# nguyen_ly.net
KiCad netlist of a schematic drawn in Altium Designer
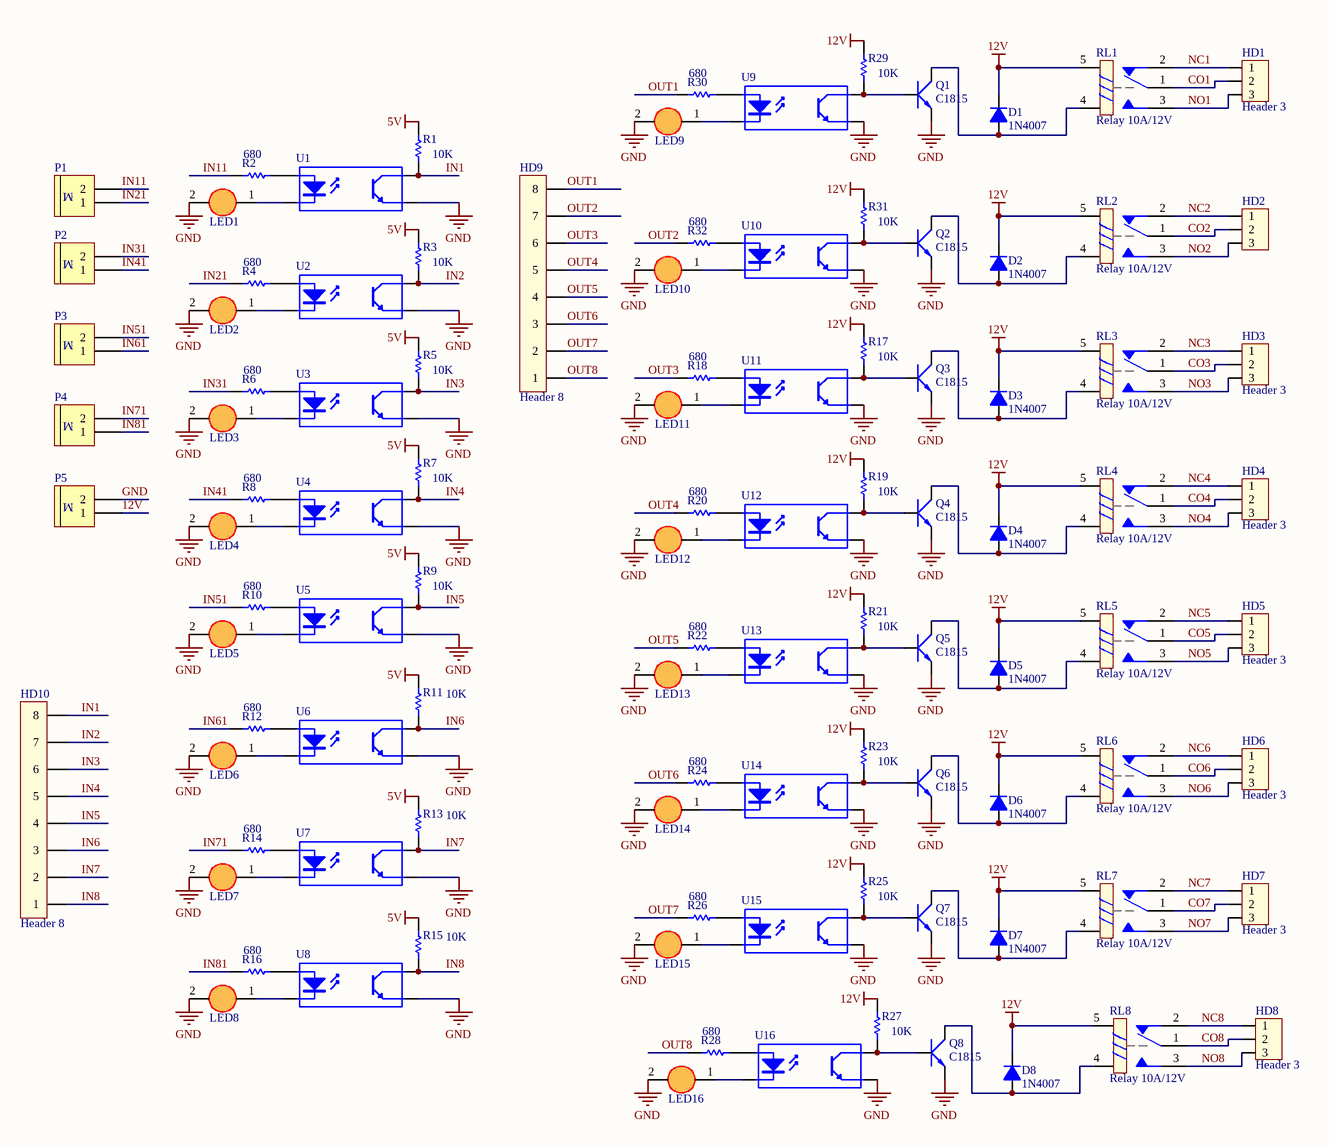
[diagram p0: nguyen ly.SchDoc]

(export (version "E")
  (design (tool "Eeschema 10.0.6"))
  (components
    (comp (ref "D1")
      (value "1N4007")
      (footprint "D1A")
      (description "Diode 1A")
      (libsource (lib "syhaunguyen") (part "D1A"))
    )
    (comp (ref "D2")
      (value "1N4007")
      (footprint "D1A")
      (description "Diode 1A")
      (libsource (lib "syhaunguyen") (part "D1A"))
    )
    (comp (ref "D3")
      (value "1N4007")
      (footprint "D1A")
      (description "Diode 1A")
      (libsource (lib "syhaunguyen") (part "D1A"))
    )
    (comp (ref "D4")
      (value "1N4007")
      (footprint "D1A")
      (description "Diode 1A")
      (libsource (lib "syhaunguyen") (part "D1A"))
    )
    (comp (ref "D5")
      (value "1N4007")
      (footprint "D1A")
      (description "Diode 1A")
      (libsource (lib "syhaunguyen") (part "D1A"))
    )
    (comp (ref "D6")
      (value "1N4007")
      (footprint "D1A")
      (description "Diode 1A")
      (libsource (lib "syhaunguyen") (part "D1A"))
    )
    (comp (ref "D7")
      (value "1N4007")
      (footprint "D1A")
      (description "Diode 1A")
      (libsource (lib "syhaunguyen") (part "D1A"))
    )
    (comp (ref "D8")
      (value "1N4007")
      (footprint "D1A")
      (description "Diode 1A")
      (libsource (lib "syhaunguyen") (part "D1A"))
    )
    (comp (ref "HD1")
      (value "Header 3")
      (footprint "HED3")
      (description "Header 3 (Green)")
      (libsource (lib "syhaunguyen") (part "Hed3"))
    )
    (comp (ref "HD2")
      (value "Header 3")
      (footprint "HED3")
      (description "Header 3 (Green)")
      (libsource (lib "syhaunguyen") (part "Hed3"))
    )
    (comp (ref "HD3")
      (value "Header 3")
      (footprint "HED3")
      (description "Header 3 (Green)")
      (libsource (lib "syhaunguyen") (part "Hed3"))
    )
    (comp (ref "HD4")
      (value "Header 3")
      (footprint "HED3")
      (description "Header 3 (Green)")
      (libsource (lib "syhaunguyen") (part "Hed3"))
    )
    (comp (ref "HD5")
      (value "Header 3")
      (footprint "HED3")
      (description "Header 3 (Green)")
      (libsource (lib "syhaunguyen") (part "Hed3"))
    )
    (comp (ref "HD6")
      (value "Header 3")
      (footprint "HED3")
      (description "Header 3 (Green)")
      (libsource (lib "syhaunguyen") (part "Hed3"))
    )
    (comp (ref "HD7")
      (value "Header 3")
      (footprint "HED3")
      (description "Header 3 (Green)")
      (libsource (lib "syhaunguyen") (part "Hed3"))
    )
    (comp (ref "HD8")
      (value "Header 3")
      (footprint "HED3")
      (description "Header 3 (Green)")
      (libsource (lib "syhaunguyen") (part "Hed3"))
    )
    (comp (ref "HD9")
      (value "Header 8")
      (footprint "HED8V")
      (description "Header 8 Vit Broad")
      (libsource (lib "syhaunguyen") (part "HED8V"))
    )
    (comp (ref "HD10")
      (value "Header 8")
      (footprint "HED8V")
      (description "Header 8 Vit Broad")
      (libsource (lib "syhaunguyen") (part "HED8V"))
    )
    (comp (ref "LED1")
      (value "LED3")
      (footprint "LED3mm")
      (description "LED 3mm")
      (libsource (lib "Cty1") (part "LED 3mm"))
    )
    (comp (ref "LED2")
      (value "LED3")
      (footprint "LED3mm")
      (description "LED 3mm")
      (libsource (lib "Cty1") (part "LED 3mm"))
    )
    (comp (ref "LED3")
      (value "LED3")
      (footprint "LED3mm")
      (description "LED 3mm")
      (libsource (lib "Cty1") (part "LED 3mm"))
    )
    (comp (ref "LED4")
      (value "LED3")
      (footprint "LED3mm")
      (description "LED 3mm")
      (libsource (lib "Cty1") (part "LED 3mm"))
    )
    (comp (ref "LED5")
      (value "LED3")
      (footprint "LED3mm")
      (description "LED 3mm")
      (libsource (lib "Cty1") (part "LED 3mm"))
    )
    (comp (ref "LED6")
      (value "LED3")
      (footprint "LED3mm")
      (description "LED 3mm")
      (libsource (lib "Cty1") (part "LED 3mm"))
    )
    (comp (ref "LED7")
      (value "LED3")
      (footprint "LED3mm")
      (description "LED 3mm")
      (libsource (lib "Cty1") (part "LED 3mm"))
    )
    (comp (ref "LED8")
      (value "LED3")
      (footprint "LED3mm")
      (description "LED 3mm")
      (libsource (lib "Cty1") (part "LED 3mm"))
    )
    (comp (ref "LED9")
      (value "LED3")
      (footprint "LED3mm")
      (description "LED 3mm")
      (libsource (lib "Cty1") (part "LED 3mm"))
    )
    (comp (ref "LED10")
      (value "LED3")
      (footprint "LED3mm")
      (description "LED 3mm")
      (libsource (lib "Cty1") (part "LED 3mm"))
    )
    (comp (ref "LED11")
      (value "LED3")
      (footprint "LED3mm")
      (description "LED 3mm")
      (libsource (lib "Cty1") (part "LED 3mm"))
    )
    (comp (ref "LED12")
      (value "LED3")
      (footprint "LED3mm")
      (description "LED 3mm")
      (libsource (lib "Cty1") (part "LED 3mm"))
    )
    (comp (ref "LED13")
      (value "LED3")
      (footprint "LED3mm")
      (description "LED 3mm")
      (libsource (lib "Cty1") (part "LED 3mm"))
    )
    (comp (ref "LED14")
      (value "LED3")
      (footprint "LED3mm")
      (description "LED 3mm")
      (libsource (lib "Cty1") (part "LED 3mm"))
    )
    (comp (ref "LED15")
      (value "LED3")
      (footprint "LED3mm")
      (description "LED 3mm")
      (libsource (lib "Cty1") (part "LED 3mm"))
    )
    (comp (ref "LED16")
      (value "LED3")
      (footprint "LED3mm")
      (description "LED 3mm")
      (libsource (lib "Cty1") (part "LED 3mm"))
    )
    (comp (ref "P1")
      (value "Header 2 - M")
      (footprint "Medium - Header 2")
      (description "Header, 2-Pin, Medium")
      (fields (field (name "PUBLISHER") "Altium Limited"))
      (libsource (lib "Cty1") (part "Header 2 - M"))
    )
    (comp (ref "P2")
      (value "Header 2 - M")
      (footprint "Medium - Header 2")
      (description "Header, 2-Pin, Medium")
      (fields (field (name "PUBLISHER") "Altium Limited"))
      (libsource (lib "Cty1") (part "Header 2 - M"))
    )
    (comp (ref "P3")
      (value "Header 2 - M")
      (footprint "Medium - Header 2")
      (description "Header, 2-Pin, Medium")
      (fields (field (name "PUBLISHER") "Altium Limited"))
      (libsource (lib "Cty1") (part "Header 2 - M"))
    )
    (comp (ref "P4")
      (value "Header 2 - M")
      (footprint "Medium - Header 2")
      (description "Header, 2-Pin, Medium")
      (fields (field (name "PUBLISHER") "Altium Limited"))
      (libsource (lib "Cty1") (part "Header 2 - M"))
    )
    (comp (ref "P5")
      (value "Header 2 - M")
      (footprint "Medium - Header 2")
      (description "Header, 2-Pin, Medium")
      (fields (field (name "PUBLISHER") "Altium Limited"))
      (libsource (lib "Cty1") (part "Header 2 - M"))
    )
    (comp (ref "Q1")
      (value "C1815")
      (footprint "QTO-92")
      (description "NPN 600mW, ECB")
      (libsource (lib "syhaunguyen") (part "C1815"))
    )
    (comp (ref "Q2")
      (value "C1815")
      (footprint "QTO-92")
      (description "NPN 600mW, ECB")
      (libsource (lib "syhaunguyen") (part "C1815"))
    )
    (comp (ref "Q3")
      (value "C1815")
      (footprint "QTO-92")
      (description "NPN 600mW, ECB")
      (libsource (lib "syhaunguyen") (part "C1815"))
    )
    (comp (ref "Q4")
      (value "C1815")
      (footprint "QTO-92")
      (description "NPN 600mW, ECB")
      (libsource (lib "syhaunguyen") (part "C1815"))
    )
    (comp (ref "Q5")
      (value "C1815")
      (footprint "QTO-92")
      (description "NPN 600mW, ECB")
      (libsource (lib "syhaunguyen") (part "C1815"))
    )
    (comp (ref "Q6")
      (value "C1815")
      (footprint "QTO-92")
      (description "NPN 600mW, ECB")
      (libsource (lib "syhaunguyen") (part "C1815"))
    )
    (comp (ref "Q7")
      (value "C1815")
      (footprint "QTO-92")
      (description "NPN 600mW, ECB")
      (libsource (lib "syhaunguyen") (part "C1815"))
    )
    (comp (ref "Q8")
      (value "C1815")
      (footprint "QTO-92")
      (description "NPN 600mW, ECB")
      (libsource (lib "syhaunguyen") (part "C1815"))
    )
    (comp (ref "R1")
      (value "10K")
      (footprint "AXIAL-0.3")
      (description "Resistor")
      (fields (field (name "Comment") "Res1") (field (name "PUBLISHER") "Altium Limited"))
      (libsource (lib "Miscellaneous Devices") (part "Res1"))
    )
    (comp (ref "R2")
      (value "680")
      (footprint "AXIAL-0.3")
      (description "Resistor")
      (fields (field (name "Comment") "Res1") (field (name "PUBLISHER") "Altium Limited"))
      (libsource (lib "Miscellaneous Devices") (part "Res1"))
    )
    (comp (ref "R3")
      (value "10K")
      (footprint "AXIAL-0.3")
      (description "Resistor")
      (fields (field (name "Comment") "Res1") (field (name "PUBLISHER") "Altium Limited"))
      (libsource (lib "Miscellaneous Devices") (part "Res1"))
    )
    (comp (ref "R4")
      (value "680")
      (footprint "AXIAL-0.3")
      (description "Resistor")
      (fields (field (name "Comment") "Res1") (field (name "PUBLISHER") "Altium Limited"))
      (libsource (lib "Miscellaneous Devices") (part "Res1"))
    )
    (comp (ref "R5")
      (value "10K")
      (footprint "AXIAL-0.3")
      (description "Resistor")
      (fields (field (name "Comment") "Res1") (field (name "PUBLISHER") "Altium Limited"))
      (libsource (lib "Miscellaneous Devices") (part "Res1"))
    )
    (comp (ref "R6")
      (value "680")
      (footprint "AXIAL-0.3")
      (description "Resistor")
      (fields (field (name "Comment") "Res1") (field (name "PUBLISHER") "Altium Limited"))
      (libsource (lib "Miscellaneous Devices") (part "Res1"))
    )
    (comp (ref "R7")
      (value "10K")
      (footprint "AXIAL-0.3")
      (description "Resistor")
      (fields (field (name "Comment") "Res1") (field (name "PUBLISHER") "Altium Limited"))
      (libsource (lib "Miscellaneous Devices") (part "Res1"))
    )
    (comp (ref "R8")
      (value "680")
      (footprint "AXIAL-0.3")
      (description "Resistor")
      (fields (field (name "Comment") "Res1") (field (name "PUBLISHER") "Altium Limited"))
      (libsource (lib "Miscellaneous Devices") (part "Res1"))
    )
    (comp (ref "R9")
      (value "10K")
      (footprint "AXIAL-0.3")
      (description "Resistor")
      (fields (field (name "Comment") "Res1") (field (name "PUBLISHER") "Altium Limited"))
      (libsource (lib "Miscellaneous Devices") (part "Res1"))
    )
    (comp (ref "R10")
      (value "680")
      (footprint "AXIAL-0.3")
      (description "Resistor")
      (fields (field (name "Comment") "Res1") (field (name "PUBLISHER") "Altium Limited"))
      (libsource (lib "Miscellaneous Devices") (part "Res1"))
    )
    (comp (ref "R11")
      (value "10K")
      (footprint "AXIAL-0.3")
      (description "Resistor")
      (fields (field (name "Comment") "Res1") (field (name "PUBLISHER") "Altium Limited"))
      (libsource (lib "Miscellaneous Devices") (part "Res1"))
    )
    (comp (ref "R12")
      (value "680")
      (footprint "AXIAL-0.3")
      (description "Resistor")
      (fields (field (name "Comment") "Res1") (field (name "PUBLISHER") "Altium Limited"))
      (libsource (lib "Miscellaneous Devices") (part "Res1"))
    )
    (comp (ref "R13")
      (value "10K")
      (footprint "AXIAL-0.3")
      (description "Resistor")
      (fields (field (name "Comment") "Res1") (field (name "PUBLISHER") "Altium Limited"))
      (libsource (lib "Miscellaneous Devices") (part "Res1"))
    )
    (comp (ref "R14")
      (value "680")
      (footprint "AXIAL-0.3")
      (description "Resistor")
      (fields (field (name "Comment") "Res1") (field (name "PUBLISHER") "Altium Limited"))
      (libsource (lib "Miscellaneous Devices") (part "Res1"))
    )
    (comp (ref "R15")
      (value "10K")
      (footprint "AXIAL-0.3")
      (description "Resistor")
      (fields (field (name "Comment") "Res1") (field (name "PUBLISHER") "Altium Limited"))
      (libsource (lib "Miscellaneous Devices") (part "Res1"))
    )
    (comp (ref "R16")
      (value "680")
      (footprint "AXIAL-0.3")
      (description "Resistor")
      (fields (field (name "Comment") "Res1") (field (name "PUBLISHER") "Altium Limited"))
      (libsource (lib "Miscellaneous Devices") (part "Res1"))
    )
    (comp (ref "R17")
      (value "10K")
      (footprint "AXIAL-0.3")
      (description "Resistor")
      (fields (field (name "Comment") "Res1") (field (name "PUBLISHER") "Altium Limited"))
      (libsource (lib "Miscellaneous Devices") (part "Res1"))
    )
    (comp (ref "R18")
      (value "680")
      (footprint "AXIAL-0.3")
      (description "Resistor")
      (fields (field (name "Comment") "Res1") (field (name "PUBLISHER") "Altium Limited"))
      (libsource (lib "Miscellaneous Devices") (part "Res1"))
    )
    (comp (ref "R19")
      (value "10K")
      (footprint "AXIAL-0.3")
      (description "Resistor")
      (fields (field (name "Comment") "Res1") (field (name "PUBLISHER") "Altium Limited"))
      (libsource (lib "Miscellaneous Devices") (part "Res1"))
    )
    (comp (ref "R20")
      (value "680")
      (footprint "AXIAL-0.3")
      (description "Resistor")
      (fields (field (name "Comment") "Res1") (field (name "PUBLISHER") "Altium Limited"))
      (libsource (lib "Miscellaneous Devices") (part "Res1"))
    )
    (comp (ref "R21")
      (value "10K")
      (footprint "AXIAL-0.3")
      (description "Resistor")
      (fields (field (name "Comment") "Res1") (field (name "PUBLISHER") "Altium Limited"))
      (libsource (lib "Miscellaneous Devices") (part "Res1"))
    )
    (comp (ref "R22")
      (value "680")
      (footprint "AXIAL-0.3")
      (description "Resistor")
      (fields (field (name "Comment") "Res1") (field (name "PUBLISHER") "Altium Limited"))
      (libsource (lib "Miscellaneous Devices") (part "Res1"))
    )
    (comp (ref "R23")
      (value "10K")
      (footprint "AXIAL-0.3")
      (description "Resistor")
      (fields (field (name "Comment") "Res1") (field (name "PUBLISHER") "Altium Limited"))
      (libsource (lib "Miscellaneous Devices") (part "Res1"))
    )
    (comp (ref "R24")
      (value "680")
      (footprint "AXIAL-0.3")
      (description "Resistor")
      (fields (field (name "Comment") "Res1") (field (name "PUBLISHER") "Altium Limited"))
      (libsource (lib "Miscellaneous Devices") (part "Res1"))
    )
    (comp (ref "R25")
      (value "10K")
      (footprint "AXIAL-0.3")
      (description "Resistor")
      (fields (field (name "Comment") "Res1") (field (name "PUBLISHER") "Altium Limited"))
      (libsource (lib "Miscellaneous Devices") (part "Res1"))
    )
    (comp (ref "R26")
      (value "680")
      (footprint "AXIAL-0.3")
      (description "Resistor")
      (fields (field (name "Comment") "Res1") (field (name "PUBLISHER") "Altium Limited"))
      (libsource (lib "Miscellaneous Devices") (part "Res1"))
    )
    (comp (ref "R27")
      (value "10K")
      (footprint "AXIAL-0.3")
      (description "Resistor")
      (fields (field (name "Comment") "Res1") (field (name "PUBLISHER") "Altium Limited"))
      (libsource (lib "Miscellaneous Devices") (part "Res1"))
    )
    (comp (ref "R28")
      (value "680")
      (footprint "AXIAL-0.3")
      (description "Resistor")
      (fields (field (name "Comment") "Res1") (field (name "PUBLISHER") "Altium Limited"))
      (libsource (lib "Miscellaneous Devices") (part "Res1"))
    )
    (comp (ref "R29")
      (value "10K")
      (footprint "AXIAL-0.3")
      (description "Resistor")
      (fields (field (name "Comment") "Res1") (field (name "PUBLISHER") "Altium Limited"))
      (libsource (lib "Miscellaneous Devices") (part "Res1"))
    )
    (comp (ref "R30")
      (value "680")
      (footprint "AXIAL-0.3")
      (description "Resistor")
      (fields (field (name "Comment") "Res1") (field (name "PUBLISHER") "Altium Limited"))
      (libsource (lib "Miscellaneous Devices") (part "Res1"))
    )
    (comp (ref "R31")
      (value "10K")
      (footprint "AXIAL-0.3")
      (description "Resistor")
      (fields (field (name "Comment") "Res1") (field (name "PUBLISHER") "Altium Limited"))
      (libsource (lib "Miscellaneous Devices") (part "Res1"))
    )
    (comp (ref "R32")
      (value "680")
      (footprint "AXIAL-0.3")
      (description "Resistor")
      (fields (field (name "Comment") "Res1") (field (name "PUBLISHER") "Altium Limited"))
      (libsource (lib "Miscellaneous Devices") (part "Res1"))
    )
    (comp (ref "RL1")
      (value "Relay 10A/12V")
      (footprint "RL_SPDT_10A")
      (description "Relay SPDT,10A - 12VDC 5 Pin")
      (libsource (lib "syhaunguyen") (part "Relay 1"))
    )
    (comp (ref "RL2")
      (value "Relay 10A/12V")
      (footprint "RL_SPDT_10A")
      (description "Relay SPDT,10A - 12VDC 5 Pin")
      (libsource (lib "syhaunguyen") (part "Relay 1"))
    )
    (comp (ref "RL3")
      (value "Relay 10A/12V")
      (footprint "RL_SPDT_10A")
      (description "Relay SPDT,10A - 12VDC 5 Pin")
      (libsource (lib "syhaunguyen") (part "Relay 1"))
    )
    (comp (ref "RL4")
      (value "Relay 10A/12V")
      (footprint "RL_SPDT_10A")
      (description "Relay SPDT,10A - 12VDC 5 Pin")
      (libsource (lib "syhaunguyen") (part "Relay 1"))
    )
    (comp (ref "RL5")
      (value "Relay 10A/12V")
      (footprint "RL_SPDT_10A")
      (description "Relay SPDT,10A - 12VDC 5 Pin")
      (libsource (lib "syhaunguyen") (part "Relay 1"))
    )
    (comp (ref "RL6")
      (value "Relay 10A/12V")
      (footprint "RL_SPDT_10A")
      (description "Relay SPDT,10A - 12VDC 5 Pin")
      (libsource (lib "syhaunguyen") (part "Relay 1"))
    )
    (comp (ref "RL7")
      (value "Relay 10A/12V")
      (footprint "RL_SPDT_10A")
      (description "Relay SPDT,10A - 12VDC 5 Pin")
      (libsource (lib "syhaunguyen") (part "Relay 1"))
    )
    (comp (ref "RL8")
      (value "Relay 10A/12V")
      (footprint "RL_SPDT_10A")
      (description "Relay SPDT,10A - 12VDC 5 Pin")
      (libsource (lib "syhaunguyen") (part "Relay 1"))
    )
    (comp (ref "U1")
      (value "Optoisolator1")
      (footprint "DIP-4")
      (description "4-Pin Phototransistor Optocoupler")
      (fields (field (name "PUBLISHER") "Altium Limited"))
      (libsource (lib "Miscellaneous Devices") (part "Optoisolator1"))
    )
    (comp (ref "U2")
      (value "Optoisolator1")
      (footprint "DIP-4")
      (description "4-Pin Phototransistor Optocoupler")
      (fields (field (name "PUBLISHER") "Altium Limited"))
      (libsource (lib "Miscellaneous Devices") (part "Optoisolator1"))
    )
    (comp (ref "U3")
      (value "Optoisolator1")
      (footprint "DIP-4")
      (description "4-Pin Phototransistor Optocoupler")
      (fields (field (name "PUBLISHER") "Altium Limited"))
      (libsource (lib "Miscellaneous Devices") (part "Optoisolator1"))
    )
    (comp (ref "U4")
      (value "Optoisolator1")
      (footprint "DIP-4")
      (description "4-Pin Phototransistor Optocoupler")
      (fields (field (name "PUBLISHER") "Altium Limited"))
      (libsource (lib "Miscellaneous Devices") (part "Optoisolator1"))
    )
    (comp (ref "U5")
      (value "Optoisolator1")
      (footprint "DIP-4")
      (description "4-Pin Phototransistor Optocoupler")
      (fields (field (name "PUBLISHER") "Altium Limited"))
      (libsource (lib "Miscellaneous Devices") (part "Optoisolator1"))
    )
    (comp (ref "U6")
      (value "Optoisolator1")
      (footprint "DIP-4")
      (description "4-Pin Phototransistor Optocoupler")
      (fields (field (name "PUBLISHER") "Altium Limited"))
      (libsource (lib "Miscellaneous Devices") (part "Optoisolator1"))
    )
    (comp (ref "U7")
      (value "Optoisolator1")
      (footprint "DIP-4")
      (description "4-Pin Phototransistor Optocoupler")
      (fields (field (name "PUBLISHER") "Altium Limited"))
      (libsource (lib "Miscellaneous Devices") (part "Optoisolator1"))
    )
    (comp (ref "U8")
      (value "Optoisolator1")
      (footprint "DIP-4")
      (description "4-Pin Phototransistor Optocoupler")
      (fields (field (name "PUBLISHER") "Altium Limited"))
      (libsource (lib "Miscellaneous Devices") (part "Optoisolator1"))
    )
    (comp (ref "U9")
      (value "Optoisolator1")
      (footprint "DIP-4")
      (description "4-Pin Phototransistor Optocoupler")
      (fields (field (name "PUBLISHER") "Altium Limited"))
      (libsource (lib "Miscellaneous Devices") (part "Optoisolator1"))
    )
    (comp (ref "U10")
      (value "Optoisolator1")
      (footprint "DIP-4")
      (description "4-Pin Phototransistor Optocoupler")
      (fields (field (name "PUBLISHER") "Altium Limited"))
      (libsource (lib "Miscellaneous Devices") (part "Optoisolator1"))
    )
    (comp (ref "U11")
      (value "Optoisolator1")
      (footprint "DIP-4")
      (description "4-Pin Phototransistor Optocoupler")
      (fields (field (name "PUBLISHER") "Altium Limited"))
      (libsource (lib "Miscellaneous Devices") (part "Optoisolator1"))
    )
    (comp (ref "U12")
      (value "Optoisolator1")
      (footprint "DIP-4")
      (description "4-Pin Phototransistor Optocoupler")
      (fields (field (name "PUBLISHER") "Altium Limited"))
      (libsource (lib "Miscellaneous Devices") (part "Optoisolator1"))
    )
    (comp (ref "U13")
      (value "Optoisolator1")
      (footprint "DIP-4")
      (description "4-Pin Phototransistor Optocoupler")
      (fields (field (name "PUBLISHER") "Altium Limited"))
      (libsource (lib "Miscellaneous Devices") (part "Optoisolator1"))
    )
    (comp (ref "U14")
      (value "Optoisolator1")
      (footprint "DIP-4")
      (description "4-Pin Phototransistor Optocoupler")
      (fields (field (name "PUBLISHER") "Altium Limited"))
      (libsource (lib "Miscellaneous Devices") (part "Optoisolator1"))
    )
    (comp (ref "U15")
      (value "Optoisolator1")
      (footprint "DIP-4")
      (description "4-Pin Phototransistor Optocoupler")
      (fields (field (name "PUBLISHER") "Altium Limited"))
      (libsource (lib "Miscellaneous Devices") (part "Optoisolator1"))
    )
    (comp (ref "U16")
      (value "Optoisolator1")
      (footprint "DIP-4")
      (description "4-Pin Phototransistor Optocoupler")
      (fields (field (name "PUBLISHER") "Altium Limited"))
      (libsource (lib "Miscellaneous Devices") (part "Optoisolator1"))
    )
  )
  (nets
    (net (code "1") (name "/CO1") (class "Default")
      (node (ref "HD1") (pin "2") (pinfunction "2_2") (pintype "passive"))
      (node (ref "RL1") (pin "1") (pinfunction "1_1") (pintype "passive"))
    )
    (net (code "2") (name "/CO2") (class "Default")
      (node (ref "HD2") (pin "2") (pinfunction "2_2") (pintype "passive"))
      (node (ref "RL2") (pin "1") (pinfunction "1_1") (pintype "passive"))
    )
    (net (code "3") (name "/CO3") (class "Default")
      (node (ref "HD3") (pin "2") (pinfunction "2_2") (pintype "passive"))
      (node (ref "RL3") (pin "1") (pinfunction "1_1") (pintype "passive"))
    )
    (net (code "4") (name "/CO4") (class "Default")
      (node (ref "HD4") (pin "2") (pinfunction "2_2") (pintype "passive"))
      (node (ref "RL4") (pin "1") (pinfunction "1_1") (pintype "passive"))
    )
    (net (code "5") (name "/CO5") (class "Default")
      (node (ref "HD5") (pin "2") (pinfunction "2_2") (pintype "passive"))
      (node (ref "RL5") (pin "1") (pinfunction "1_1") (pintype "passive"))
    )
    (net (code "6") (name "/CO6") (class "Default")
      (node (ref "HD6") (pin "2") (pinfunction "2_2") (pintype "passive"))
      (node (ref "RL6") (pin "1") (pinfunction "1_1") (pintype "passive"))
    )
    (net (code "7") (name "/CO7") (class "Default")
      (node (ref "HD7") (pin "2") (pinfunction "2_2") (pintype "passive"))
      (node (ref "RL7") (pin "1") (pinfunction "1_1") (pintype "passive"))
    )
    (net (code "8") (name "/CO8") (class "Default")
      (node (ref "HD8") (pin "2") (pinfunction "2_2") (pintype "passive"))
      (node (ref "RL8") (pin "1") (pinfunction "1_1") (pintype "passive"))
    )
    (net (code "9") (name "/IN1") (class "Default")
      (node (ref "HD10") (pin "8") (pinfunction "8_8") (pintype "passive"))
      (node (ref "R1") (pin "1") (pinfunction "1_1") (pintype "passive"))
      (node (ref "U1") (pin "4") (pinfunction "C_4") (pintype "passive"))
    )
    (net (code "10") (name "/IN2") (class "Default")
      (node (ref "HD10") (pin "7") (pinfunction "7_7") (pintype "passive"))
      (node (ref "R3") (pin "1") (pinfunction "1_1") (pintype "passive"))
      (node (ref "U2") (pin "4") (pinfunction "C_4") (pintype "passive"))
    )
    (net (code "11") (name "/IN3") (class "Default")
      (node (ref "HD10") (pin "6") (pinfunction "6_6") (pintype "passive"))
      (node (ref "R5") (pin "1") (pinfunction "1_1") (pintype "passive"))
      (node (ref "U3") (pin "4") (pinfunction "C_4") (pintype "passive"))
    )
    (net (code "12") (name "/IN4") (class "Default")
      (node (ref "HD10") (pin "5") (pinfunction "5_5") (pintype "passive"))
      (node (ref "R7") (pin "1") (pinfunction "1_1") (pintype "passive"))
      (node (ref "U4") (pin "4") (pinfunction "C_4") (pintype "passive"))
    )
    (net (code "13") (name "/IN5") (class "Default")
      (node (ref "HD10") (pin "4") (pinfunction "4_4") (pintype "passive"))
      (node (ref "R9") (pin "1") (pinfunction "1_1") (pintype "passive"))
      (node (ref "U5") (pin "4") (pinfunction "C_4") (pintype "passive"))
    )
    (net (code "14") (name "/IN6") (class "Default")
      (node (ref "HD10") (pin "3") (pinfunction "3_3") (pintype "passive"))
      (node (ref "R11") (pin "1") (pinfunction "1_1") (pintype "passive"))
      (node (ref "U6") (pin "4") (pinfunction "C_4") (pintype "passive"))
    )
    (net (code "15") (name "/IN7") (class "Default")
      (node (ref "HD10") (pin "2") (pinfunction "2_2") (pintype "passive"))
      (node (ref "R13") (pin "1") (pinfunction "1_1") (pintype "passive"))
      (node (ref "U7") (pin "4") (pinfunction "C_4") (pintype "passive"))
    )
    (net (code "16") (name "/IN8") (class "Default")
      (node (ref "HD10") (pin "1") (pinfunction "1_1") (pintype "passive"))
      (node (ref "R15") (pin "1") (pinfunction "1_1") (pintype "passive"))
      (node (ref "U8") (pin "4") (pinfunction "C_4") (pintype "passive"))
    )
    (net (code "17") (name "/IN11") (class "Default")
      (node (ref "P1") (pin "2") (pinfunction "2_2") (pintype "passive"))
      (node (ref "R2") (pin "1") (pinfunction "1_1") (pintype "passive"))
    )
    (net (code "18") (name "/IN21") (class "Default")
      (node (ref "P1") (pin "1") (pinfunction "1_1") (pintype "passive"))
      (node (ref "R4") (pin "1") (pinfunction "1_1") (pintype "passive"))
    )
    (net (code "19") (name "/IN31") (class "Default")
      (node (ref "P2") (pin "2") (pinfunction "2_2") (pintype "passive"))
      (node (ref "R6") (pin "1") (pinfunction "1_1") (pintype "passive"))
    )
    (net (code "20") (name "/IN41") (class "Default")
      (node (ref "P2") (pin "1") (pinfunction "1_1") (pintype "passive"))
      (node (ref "R8") (pin "1") (pinfunction "1_1") (pintype "passive"))
    )
    (net (code "21") (name "/IN51") (class "Default")
      (node (ref "P3") (pin "2") (pinfunction "2_2") (pintype "passive"))
      (node (ref "R10") (pin "1") (pinfunction "1_1") (pintype "passive"))
    )
    (net (code "22") (name "/IN61") (class "Default")
      (node (ref "P3") (pin "1") (pinfunction "1_1") (pintype "passive"))
      (node (ref "R12") (pin "1") (pinfunction "1_1") (pintype "passive"))
    )
    (net (code "23") (name "/IN71") (class "Default")
      (node (ref "P4") (pin "2") (pinfunction "2_2") (pintype "passive"))
      (node (ref "R14") (pin "1") (pinfunction "1_1") (pintype "passive"))
    )
    (net (code "24") (name "/IN81") (class "Default")
      (node (ref "P4") (pin "1") (pinfunction "1_1") (pintype "passive"))
      (node (ref "R16") (pin "1") (pinfunction "1_1") (pintype "passive"))
    )
    (net (code "25") (name "/NC1") (class "Default")
      (node (ref "HD1") (pin "1") (pinfunction "1_1") (pintype "passive"))
      (node (ref "RL1") (pin "2") (pinfunction "2_2") (pintype "passive"))
    )
    (net (code "26") (name "/NC2") (class "Default")
      (node (ref "HD2") (pin "1") (pinfunction "1_1") (pintype "passive"))
      (node (ref "RL2") (pin "2") (pinfunction "2_2") (pintype "passive"))
    )
    (net (code "27") (name "/NC3") (class "Default")
      (node (ref "HD3") (pin "1") (pinfunction "1_1") (pintype "passive"))
      (node (ref "RL3") (pin "2") (pinfunction "2_2") (pintype "passive"))
    )
    (net (code "28") (name "/NC4") (class "Default")
      (node (ref "HD4") (pin "1") (pinfunction "1_1") (pintype "passive"))
      (node (ref "RL4") (pin "2") (pinfunction "2_2") (pintype "passive"))
    )
    (net (code "29") (name "/NC5") (class "Default")
      (node (ref "HD5") (pin "1") (pinfunction "1_1") (pintype "passive"))
      (node (ref "RL5") (pin "2") (pinfunction "2_2") (pintype "passive"))
    )
    (net (code "30") (name "/NC6") (class "Default")
      (node (ref "HD6") (pin "1") (pinfunction "1_1") (pintype "passive"))
      (node (ref "RL6") (pin "2") (pinfunction "2_2") (pintype "passive"))
    )
    (net (code "31") (name "/NC7") (class "Default")
      (node (ref "HD7") (pin "1") (pinfunction "1_1") (pintype "passive"))
      (node (ref "RL7") (pin "2") (pinfunction "2_2") (pintype "passive"))
    )
    (net (code "32") (name "/NC8") (class "Default")
      (node (ref "HD8") (pin "1") (pinfunction "1_1") (pintype "passive"))
      (node (ref "RL8") (pin "2") (pinfunction "2_2") (pintype "passive"))
    )
    (net (code "33") (name "/NO1") (class "Default")
      (node (ref "HD1") (pin "3") (pinfunction "3_3") (pintype "passive"))
      (node (ref "RL1") (pin "3") (pinfunction "3_3") (pintype "passive"))
    )
    (net (code "34") (name "/NO2") (class "Default")
      (node (ref "HD2") (pin "3") (pinfunction "3_3") (pintype "passive"))
      (node (ref "RL2") (pin "3") (pinfunction "3_3") (pintype "passive"))
    )
    (net (code "35") (name "/NO3") (class "Default")
      (node (ref "HD3") (pin "3") (pinfunction "3_3") (pintype "passive"))
      (node (ref "RL3") (pin "3") (pinfunction "3_3") (pintype "passive"))
    )
    (net (code "36") (name "/NO4") (class "Default")
      (node (ref "HD4") (pin "3") (pinfunction "3_3") (pintype "passive"))
      (node (ref "RL4") (pin "3") (pinfunction "3_3") (pintype "passive"))
    )
    (net (code "37") (name "/NO5") (class "Default")
      (node (ref "HD5") (pin "3") (pinfunction "3_3") (pintype "passive"))
      (node (ref "RL5") (pin "3") (pinfunction "3_3") (pintype "passive"))
    )
    (net (code "38") (name "/NO6") (class "Default")
      (node (ref "HD6") (pin "3") (pinfunction "3_3") (pintype "passive"))
      (node (ref "RL6") (pin "3") (pinfunction "3_3") (pintype "passive"))
    )
    (net (code "39") (name "/NO7") (class "Default")
      (node (ref "HD7") (pin "3") (pinfunction "3_3") (pintype "passive"))
      (node (ref "RL7") (pin "3") (pinfunction "3_3") (pintype "passive"))
    )
    (net (code "40") (name "/NO8") (class "Default")
      (node (ref "HD8") (pin "3") (pinfunction "3_3") (pintype "passive"))
      (node (ref "RL8") (pin "3") (pinfunction "3_3") (pintype "passive"))
    )
    (net (code "41") (name "/OUT1") (class "Default")
      (node (ref "HD9") (pin "8") (pinfunction "8_8") (pintype "passive"))
      (node (ref "R30") (pin "1") (pinfunction "1_1") (pintype "passive"))
    )
    (net (code "42") (name "/OUT2") (class "Default")
      (node (ref "HD9") (pin "7") (pinfunction "7_7") (pintype "passive"))
      (node (ref "R32") (pin "1") (pinfunction "1_1") (pintype "passive"))
    )
    (net (code "43") (name "/OUT3") (class "Default")
      (node (ref "HD9") (pin "6") (pinfunction "6_6") (pintype "passive"))
      (node (ref "R18") (pin "1") (pinfunction "1_1") (pintype "passive"))
    )
    (net (code "44") (name "/OUT4") (class "Default")
      (node (ref "HD9") (pin "5") (pinfunction "5_5") (pintype "passive"))
      (node (ref "R20") (pin "1") (pinfunction "1_1") (pintype "passive"))
    )
    (net (code "45") (name "/OUT5") (class "Default")
      (node (ref "HD9") (pin "4") (pinfunction "4_4") (pintype "passive"))
      (node (ref "R22") (pin "1") (pinfunction "1_1") (pintype "passive"))
    )
    (net (code "46") (name "/OUT6") (class "Default")
      (node (ref "HD9") (pin "3") (pinfunction "3_3") (pintype "passive"))
      (node (ref "R24") (pin "1") (pinfunction "1_1") (pintype "passive"))
    )
    (net (code "47") (name "/OUT7") (class "Default")
      (node (ref "HD9") (pin "2") (pinfunction "2_2") (pintype "passive"))
      (node (ref "R26") (pin "1") (pinfunction "1_1") (pintype "passive"))
    )
    (net (code "48") (name "/OUT8") (class "Default")
      (node (ref "HD9") (pin "1") (pinfunction "1_1") (pintype "passive"))
      (node (ref "R28") (pin "1") (pinfunction "1_1") (pintype "passive"))
    )
    (net (code "49") (name "5V") (class "Default")
      (node (ref "R1") (pin "2") (pinfunction "2_2") (pintype "passive"))
      (node (ref "R11") (pin "2") (pinfunction "2_2") (pintype "passive"))
      (node (ref "R13") (pin "2") (pinfunction "2_2") (pintype "passive"))
      (node (ref "R15") (pin "2") (pinfunction "2_2") (pintype "passive"))
      (node (ref "R3") (pin "2") (pinfunction "2_2") (pintype "passive"))
      (node (ref "R5") (pin "2") (pinfunction "2_2") (pintype "passive"))
      (node (ref "R7") (pin "2") (pinfunction "2_2") (pintype "passive"))
      (node (ref "R9") (pin "2") (pinfunction "2_2") (pintype "passive"))
    )
    (net (code "50") (name "12V") (class "Default")
      (node (ref "D1") (pin "2") (pinfunction "K_2") (pintype "passive"))
      (node (ref "D2") (pin "2") (pinfunction "K_2") (pintype "passive"))
      (node (ref "D3") (pin "2") (pinfunction "K_2") (pintype "passive"))
      (node (ref "D4") (pin "2") (pinfunction "K_2") (pintype "passive"))
      (node (ref "D5") (pin "2") (pinfunction "K_2") (pintype "passive"))
      (node (ref "D6") (pin "2") (pinfunction "K_2") (pintype "passive"))
      (node (ref "D7") (pin "2") (pinfunction "K_2") (pintype "passive"))
      (node (ref "D8") (pin "2") (pinfunction "K_2") (pintype "passive"))
      (node (ref "P5") (pin "1") (pinfunction "1_1") (pintype "passive"))
      (node (ref "R17") (pin "2") (pinfunction "2_2") (pintype "passive"))
      (node (ref "R19") (pin "2") (pinfunction "2_2") (pintype "passive"))
      (node (ref "R21") (pin "2") (pinfunction "2_2") (pintype "passive"))
      (node (ref "R23") (pin "2") (pinfunction "2_2") (pintype "passive"))
      (node (ref "R25") (pin "2") (pinfunction "2_2") (pintype "passive"))
      (node (ref "R27") (pin "2") (pinfunction "2_2") (pintype "passive"))
      (node (ref "R29") (pin "2") (pinfunction "2_2") (pintype "passive"))
      (node (ref "R31") (pin "2") (pinfunction "2_2") (pintype "passive"))
      (node (ref "RL1") (pin "5") (pinfunction "5_5") (pintype "passive"))
      (node (ref "RL2") (pin "5") (pinfunction "5_5") (pintype "passive"))
      (node (ref "RL3") (pin "5") (pinfunction "5_5") (pintype "passive"))
      (node (ref "RL4") (pin "5") (pinfunction "5_5") (pintype "passive"))
      (node (ref "RL5") (pin "5") (pinfunction "5_5") (pintype "passive"))
      (node (ref "RL6") (pin "5") (pinfunction "5_5") (pintype "passive"))
      (node (ref "RL7") (pin "5") (pinfunction "5_5") (pintype "passive"))
      (node (ref "RL8") (pin "5") (pinfunction "5_5") (pintype "passive"))
    )
    (net (code "51") (name "GND") (class "Default")
      (node (ref "LED1") (pin "2") (pinfunction "K_2") (pintype "passive"))
      (node (ref "LED10") (pin "2") (pinfunction "K_2") (pintype "passive"))
      (node (ref "LED11") (pin "2") (pinfunction "K_2") (pintype "passive"))
      (node (ref "LED12") (pin "2") (pinfunction "K_2") (pintype "passive"))
      (node (ref "LED13") (pin "2") (pinfunction "K_2") (pintype "passive"))
      (node (ref "LED14") (pin "2") (pinfunction "K_2") (pintype "passive"))
      (node (ref "LED15") (pin "2") (pinfunction "K_2") (pintype "passive"))
      (node (ref "LED16") (pin "2") (pinfunction "K_2") (pintype "passive"))
      (node (ref "LED2") (pin "2") (pinfunction "K_2") (pintype "passive"))
      (node (ref "LED3") (pin "2") (pinfunction "K_2") (pintype "passive"))
      (node (ref "LED4") (pin "2") (pinfunction "K_2") (pintype "passive"))
      (node (ref "LED5") (pin "2") (pinfunction "K_2") (pintype "passive"))
      (node (ref "LED6") (pin "2") (pinfunction "K_2") (pintype "passive"))
      (node (ref "LED7") (pin "2") (pinfunction "K_2") (pintype "passive"))
      (node (ref "LED8") (pin "2") (pinfunction "K_2") (pintype "passive"))
      (node (ref "LED9") (pin "2") (pinfunction "K_2") (pintype "passive"))
      (node (ref "P5") (pin "2") (pinfunction "2_2") (pintype "passive"))
      (node (ref "Q1") (pin "1") (pinfunction "E_1") (pintype "passive"))
      (node (ref "Q2") (pin "1") (pinfunction "E_1") (pintype "passive"))
      (node (ref "Q3") (pin "1") (pinfunction "E_1") (pintype "passive"))
      (node (ref "Q4") (pin "1") (pinfunction "E_1") (pintype "passive"))
      (node (ref "Q5") (pin "1") (pinfunction "E_1") (pintype "passive"))
      (node (ref "Q6") (pin "1") (pinfunction "E_1") (pintype "passive"))
      (node (ref "Q7") (pin "1") (pinfunction "E_1") (pintype "passive"))
      (node (ref "Q8") (pin "1") (pinfunction "E_1") (pintype "passive"))
      (node (ref "U1") (pin "3") (pinfunction "E_3") (pintype "passive"))
      (node (ref "U10") (pin "3") (pinfunction "E_3") (pintype "passive"))
      (node (ref "U11") (pin "3") (pinfunction "E_3") (pintype "passive"))
      (node (ref "U12") (pin "3") (pinfunction "E_3") (pintype "passive"))
      (node (ref "U13") (pin "3") (pinfunction "E_3") (pintype "passive"))
      (node (ref "U14") (pin "3") (pinfunction "E_3") (pintype "passive"))
      (node (ref "U15") (pin "3") (pinfunction "E_3") (pintype "passive"))
      (node (ref "U16") (pin "3") (pinfunction "E_3") (pintype "passive"))
      (node (ref "U2") (pin "3") (pinfunction "E_3") (pintype "passive"))
      (node (ref "U3") (pin "3") (pinfunction "E_3") (pintype "passive"))
      (node (ref "U4") (pin "3") (pinfunction "E_3") (pintype "passive"))
      (node (ref "U5") (pin "3") (pinfunction "E_3") (pintype "passive"))
      (node (ref "U6") (pin "3") (pinfunction "E_3") (pintype "passive"))
      (node (ref "U7") (pin "3") (pinfunction "E_3") (pintype "passive"))
      (node (ref "U8") (pin "3") (pinfunction "E_3") (pintype "passive"))
      (node (ref "U9") (pin "3") (pinfunction "E_3") (pintype "passive"))
    )
    (net (code "52") (name "Net-(D1-A)") (class "Default")
      (node (ref "D1") (pin "1") (pinfunction "A_1") (pintype "passive"))
      (node (ref "Q1") (pin "2") (pinfunction "C_2") (pintype "passive"))
      (node (ref "RL1") (pin "4") (pinfunction "4_4") (pintype "passive"))
    )
    (net (code "53") (name "Net-(D2-A)") (class "Default")
      (node (ref "D2") (pin "1") (pinfunction "A_1") (pintype "passive"))
      (node (ref "Q2") (pin "2") (pinfunction "C_2") (pintype "passive"))
      (node (ref "RL2") (pin "4") (pinfunction "4_4") (pintype "passive"))
    )
    (net (code "54") (name "Net-(D3-A)") (class "Default")
      (node (ref "D3") (pin "1") (pinfunction "A_1") (pintype "passive"))
      (node (ref "Q3") (pin "2") (pinfunction "C_2") (pintype "passive"))
      (node (ref "RL3") (pin "4") (pinfunction "4_4") (pintype "passive"))
    )
    (net (code "55") (name "Net-(D4-A)") (class "Default")
      (node (ref "D4") (pin "1") (pinfunction "A_1") (pintype "passive"))
      (node (ref "Q4") (pin "2") (pinfunction "C_2") (pintype "passive"))
      (node (ref "RL4") (pin "4") (pinfunction "4_4") (pintype "passive"))
    )
    (net (code "56") (name "Net-(D5-A)") (class "Default")
      (node (ref "D5") (pin "1") (pinfunction "A_1") (pintype "passive"))
      (node (ref "Q5") (pin "2") (pinfunction "C_2") (pintype "passive"))
      (node (ref "RL5") (pin "4") (pinfunction "4_4") (pintype "passive"))
    )
    (net (code "57") (name "Net-(D6-A)") (class "Default")
      (node (ref "D6") (pin "1") (pinfunction "A_1") (pintype "passive"))
      (node (ref "Q6") (pin "2") (pinfunction "C_2") (pintype "passive"))
      (node (ref "RL6") (pin "4") (pinfunction "4_4") (pintype "passive"))
    )
    (net (code "58") (name "Net-(D7-A)") (class "Default")
      (node (ref "D7") (pin "1") (pinfunction "A_1") (pintype "passive"))
      (node (ref "Q7") (pin "2") (pinfunction "C_2") (pintype "passive"))
      (node (ref "RL7") (pin "4") (pinfunction "4_4") (pintype "passive"))
    )
    (net (code "59") (name "Net-(D8-A)") (class "Default")
      (node (ref "D8") (pin "1") (pinfunction "A_1") (pintype "passive"))
      (node (ref "Q8") (pin "2") (pinfunction "C_2") (pintype "passive"))
      (node (ref "RL8") (pin "4") (pinfunction "4_4") (pintype "passive"))
    )
    (net (code "60") (name "Net-(LED1-A)") (class "Default")
      (node (ref "LED1") (pin "1") (pinfunction "A_1") (pintype "passive"))
      (node (ref "U1") (pin "2") (pinfunction "K_2") (pintype "passive"))
    )
    (net (code "61") (name "Net-(LED2-A)") (class "Default")
      (node (ref "LED2") (pin "1") (pinfunction "A_1") (pintype "passive"))
      (node (ref "U2") (pin "2") (pinfunction "K_2") (pintype "passive"))
    )
    (net (code "62") (name "Net-(LED3-A)") (class "Default")
      (node (ref "LED3") (pin "1") (pinfunction "A_1") (pintype "passive"))
      (node (ref "U3") (pin "2") (pinfunction "K_2") (pintype "passive"))
    )
    (net (code "63") (name "Net-(LED4-A)") (class "Default")
      (node (ref "LED4") (pin "1") (pinfunction "A_1") (pintype "passive"))
      (node (ref "U4") (pin "2") (pinfunction "K_2") (pintype "passive"))
    )
    (net (code "64") (name "Net-(LED5-A)") (class "Default")
      (node (ref "LED5") (pin "1") (pinfunction "A_1") (pintype "passive"))
      (node (ref "U5") (pin "2") (pinfunction "K_2") (pintype "passive"))
    )
    (net (code "65") (name "Net-(LED6-A)") (class "Default")
      (node (ref "LED6") (pin "1") (pinfunction "A_1") (pintype "passive"))
      (node (ref "U6") (pin "2") (pinfunction "K_2") (pintype "passive"))
    )
    (net (code "66") (name "Net-(LED7-A)") (class "Default")
      (node (ref "LED7") (pin "1") (pinfunction "A_1") (pintype "passive"))
      (node (ref "U7") (pin "2") (pinfunction "K_2") (pintype "passive"))
    )
    (net (code "67") (name "Net-(LED8-A)") (class "Default")
      (node (ref "LED8") (pin "1") (pinfunction "A_1") (pintype "passive"))
      (node (ref "U8") (pin "2") (pinfunction "K_2") (pintype "passive"))
    )
    (net (code "68") (name "Net-(LED9-A)") (class "Default")
      (node (ref "LED9") (pin "1") (pinfunction "A_1") (pintype "passive"))
      (node (ref "U9") (pin "2") (pinfunction "K_2") (pintype "passive"))
    )
    (net (code "69") (name "Net-(LED10-A)") (class "Default")
      (node (ref "LED10") (pin "1") (pinfunction "A_1") (pintype "passive"))
      (node (ref "U10") (pin "2") (pinfunction "K_2") (pintype "passive"))
    )
    (net (code "70") (name "Net-(LED11-A)") (class "Default")
      (node (ref "LED11") (pin "1") (pinfunction "A_1") (pintype "passive"))
      (node (ref "U11") (pin "2") (pinfunction "K_2") (pintype "passive"))
    )
    (net (code "71") (name "Net-(LED12-A)") (class "Default")
      (node (ref "LED12") (pin "1") (pinfunction "A_1") (pintype "passive"))
      (node (ref "U12") (pin "2") (pinfunction "K_2") (pintype "passive"))
    )
    (net (code "72") (name "Net-(LED13-A)") (class "Default")
      (node (ref "LED13") (pin "1") (pinfunction "A_1") (pintype "passive"))
      (node (ref "U13") (pin "2") (pinfunction "K_2") (pintype "passive"))
    )
    (net (code "73") (name "Net-(LED14-A)") (class "Default")
      (node (ref "LED14") (pin "1") (pinfunction "A_1") (pintype "passive"))
      (node (ref "U14") (pin "2") (pinfunction "K_2") (pintype "passive"))
    )
    (net (code "74") (name "Net-(LED15-A)") (class "Default")
      (node (ref "LED15") (pin "1") (pinfunction "A_1") (pintype "passive"))
      (node (ref "U15") (pin "2") (pinfunction "K_2") (pintype "passive"))
    )
    (net (code "75") (name "Net-(LED16-A)") (class "Default")
      (node (ref "LED16") (pin "1") (pinfunction "A_1") (pintype "passive"))
      (node (ref "U16") (pin "2") (pinfunction "K_2") (pintype "passive"))
    )
    (net (code "76") (name "Net-(Q1-B)") (class "Default")
      (node (ref "Q1") (pin "3") (pinfunction "B_3") (pintype "passive"))
      (node (ref "R29") (pin "1") (pinfunction "1_1") (pintype "passive"))
      (node (ref "U9") (pin "4") (pinfunction "C_4") (pintype "passive"))
    )
    (net (code "77") (name "Net-(Q2-B)") (class "Default")
      (node (ref "Q2") (pin "3") (pinfunction "B_3") (pintype "passive"))
      (node (ref "R31") (pin "1") (pinfunction "1_1") (pintype "passive"))
      (node (ref "U10") (pin "4") (pinfunction "C_4") (pintype "passive"))
    )
    (net (code "78") (name "Net-(Q3-B)") (class "Default")
      (node (ref "Q3") (pin "3") (pinfunction "B_3") (pintype "passive"))
      (node (ref "R17") (pin "1") (pinfunction "1_1") (pintype "passive"))
      (node (ref "U11") (pin "4") (pinfunction "C_4") (pintype "passive"))
    )
    (net (code "79") (name "Net-(Q4-B)") (class "Default")
      (node (ref "Q4") (pin "3") (pinfunction "B_3") (pintype "passive"))
      (node (ref "R19") (pin "1") (pinfunction "1_1") (pintype "passive"))
      (node (ref "U12") (pin "4") (pinfunction "C_4") (pintype "passive"))
    )
    (net (code "80") (name "Net-(Q5-B)") (class "Default")
      (node (ref "Q5") (pin "3") (pinfunction "B_3") (pintype "passive"))
      (node (ref "R21") (pin "1") (pinfunction "1_1") (pintype "passive"))
      (node (ref "U13") (pin "4") (pinfunction "C_4") (pintype "passive"))
    )
    (net (code "81") (name "Net-(Q6-B)") (class "Default")
      (node (ref "Q6") (pin "3") (pinfunction "B_3") (pintype "passive"))
      (node (ref "R23") (pin "1") (pinfunction "1_1") (pintype "passive"))
      (node (ref "U14") (pin "4") (pinfunction "C_4") (pintype "passive"))
    )
    (net (code "82") (name "Net-(Q7-B)") (class "Default")
      (node (ref "Q7") (pin "3") (pinfunction "B_3") (pintype "passive"))
      (node (ref "R25") (pin "1") (pinfunction "1_1") (pintype "passive"))
      (node (ref "U15") (pin "4") (pinfunction "C_4") (pintype "passive"))
    )
    (net (code "83") (name "Net-(Q8-B)") (class "Default")
      (node (ref "Q8") (pin "3") (pinfunction "B_3") (pintype "passive"))
      (node (ref "R27") (pin "1") (pinfunction "1_1") (pintype "passive"))
      (node (ref "U16") (pin "4") (pinfunction "C_4") (pintype "passive"))
    )
    (net (code "84") (name "Net-(U1-A)") (class "Default")
      (node (ref "R2") (pin "2") (pinfunction "2_2") (pintype "passive"))
      (node (ref "U1") (pin "1") (pinfunction "A_1") (pintype "passive"))
    )
    (net (code "85") (name "Net-(U2-A)") (class "Default")
      (node (ref "R4") (pin "2") (pinfunction "2_2") (pintype "passive"))
      (node (ref "U2") (pin "1") (pinfunction "A_1") (pintype "passive"))
    )
    (net (code "86") (name "Net-(U3-A)") (class "Default")
      (node (ref "R6") (pin "2") (pinfunction "2_2") (pintype "passive"))
      (node (ref "U3") (pin "1") (pinfunction "A_1") (pintype "passive"))
    )
    (net (code "87") (name "Net-(U4-A)") (class "Default")
      (node (ref "R8") (pin "2") (pinfunction "2_2") (pintype "passive"))
      (node (ref "U4") (pin "1") (pinfunction "A_1") (pintype "passive"))
    )
    (net (code "88") (name "Net-(U5-A)") (class "Default")
      (node (ref "R10") (pin "2") (pinfunction "2_2") (pintype "passive"))
      (node (ref "U5") (pin "1") (pinfunction "A_1") (pintype "passive"))
    )
    (net (code "89") (name "Net-(U6-A)") (class "Default")
      (node (ref "R12") (pin "2") (pinfunction "2_2") (pintype "passive"))
      (node (ref "U6") (pin "1") (pinfunction "A_1") (pintype "passive"))
    )
    (net (code "90") (name "Net-(U7-A)") (class "Default")
      (node (ref "R14") (pin "2") (pinfunction "2_2") (pintype "passive"))
      (node (ref "U7") (pin "1") (pinfunction "A_1") (pintype "passive"))
    )
    (net (code "91") (name "Net-(U8-A)") (class "Default")
      (node (ref "R16") (pin "2") (pinfunction "2_2") (pintype "passive"))
      (node (ref "U8") (pin "1") (pinfunction "A_1") (pintype "passive"))
    )
    (net (code "92") (name "Net-(U9-A)") (class "Default")
      (node (ref "R30") (pin "2") (pinfunction "2_2") (pintype "passive"))
      (node (ref "U9") (pin "1") (pinfunction "A_1") (pintype "passive"))
    )
    (net (code "93") (name "Net-(U10-A)") (class "Default")
      (node (ref "R32") (pin "2") (pinfunction "2_2") (pintype "passive"))
      (node (ref "U10") (pin "1") (pinfunction "A_1") (pintype "passive"))
    )
    (net (code "94") (name "Net-(U11-A)") (class "Default")
      (node (ref "R18") (pin "2") (pinfunction "2_2") (pintype "passive"))
      (node (ref "U11") (pin "1") (pinfunction "A_1") (pintype "passive"))
    )
    (net (code "95") (name "Net-(U12-A)") (class "Default")
      (node (ref "R20") (pin "2") (pinfunction "2_2") (pintype "passive"))
      (node (ref "U12") (pin "1") (pinfunction "A_1") (pintype "passive"))
    )
    (net (code "96") (name "Net-(U13-A)") (class "Default")
      (node (ref "R22") (pin "2") (pinfunction "2_2") (pintype "passive"))
      (node (ref "U13") (pin "1") (pinfunction "A_1") (pintype "passive"))
    )
    (net (code "97") (name "Net-(U14-A)") (class "Default")
      (node (ref "R24") (pin "2") (pinfunction "2_2") (pintype "passive"))
      (node (ref "U14") (pin "1") (pinfunction "A_1") (pintype "passive"))
    )
    (net (code "98") (name "Net-(U15-A)") (class "Default")
      (node (ref "R26") (pin "2") (pinfunction "2_2") (pintype "passive"))
      (node (ref "U15") (pin "1") (pinfunction "A_1") (pintype "passive"))
    )
    (net (code "99") (name "Net-(U16-A)") (class "Default")
      (node (ref "R28") (pin "2") (pinfunction "2_2") (pintype "passive"))
      (node (ref "U16") (pin "1") (pinfunction "A_1") (pintype "passive"))
    )
  )
)
